# SDcard.net
KiCad netlist of a schematic drawn in Altium Designer
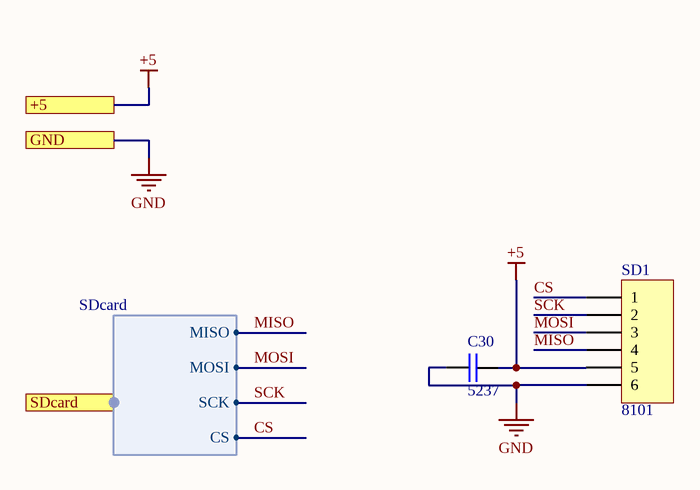
[diagram p0: SDcard.SchDoc]

(export (version "E")
  (design (tool "Eeschema 10.0.6"))
  (components
    (comp (ref "C30")
      (value "1u'F, 50'V")
      (footprint "CAP 1206/3216")
      (description "Bipolar ceramic capacitor SMD")
      (fields (field (name "INFLOW") "5237") (field (name "VALIDATION") "Valid"))
      (libsource (lib "aKaReZa") (part "Cap_Multi_1u_50_1206"))
    )
    (comp (ref "SD1")
      (value "6")
      (footprint "HDR_THT_6F_2.54mm")
      (description "Header, single row, 6 pin")
      (fields (field (name "INFLOW") "8101") (field (name "VALIDATION") "NT"))
      (libsource (lib "aKaReZa") (part "Con_FPH_6x1_V_THT_2.54"))
    )
  )
  (nets
    (net (code "2") (name "+5") (class "Default")
      (node (ref "C30") (pin "2") (pinfunction "2_2") (pintype "passive"))
      (node (ref "SD1") (pin "5") (pinfunction "5_5") (pintype "passive"))
    )
    (net (code "3") (name "/CS") (class "Default")
      (node (ref "SD1") (pin "1") (pinfunction "1_1") (pintype "passive"))
    )
    (net (code "4") (name "/MISO") (class "Default")
      (node (ref "SD1") (pin "4") (pinfunction "4_4") (pintype "passive"))
    )
    (net (code "5") (name "/MOSI") (class "Default")
      (node (ref "SD1") (pin "3") (pinfunction "3_3") (pintype "passive"))
    )
    (net (code "6") (name "/SCK") (class "Default")
      (node (ref "SD1") (pin "2") (pinfunction "2_2") (pintype "passive"))
    )
    (net (code "8") (name "GND") (class "Default")
      (node (ref "C30") (pin "1") (pinfunction "1_1") (pintype "passive"))
      (node (ref "SD1") (pin "6") (pinfunction "6_6") (pintype "passive"))
    )
  )
)
